# 1high.net
KiCad netlist of a schematic drawn in EAGLE
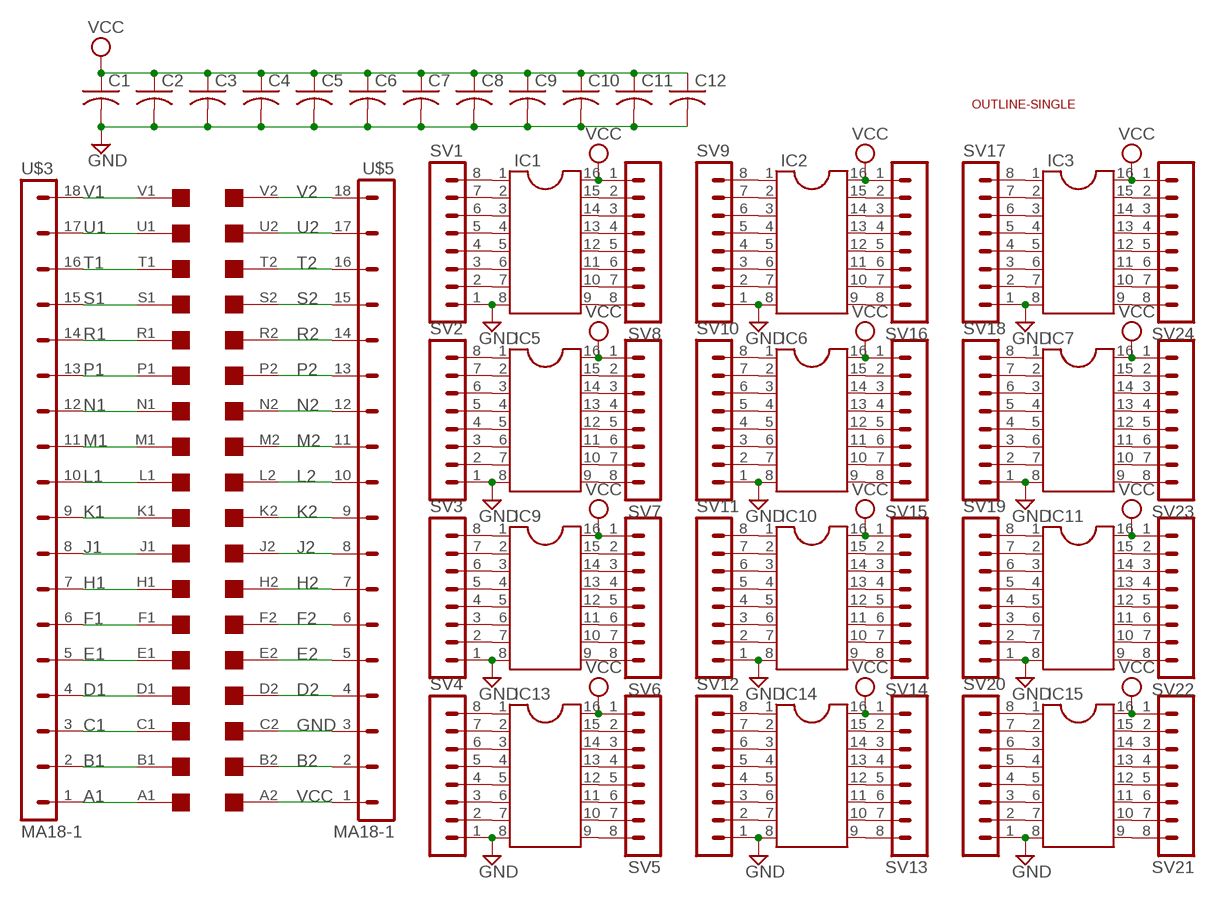
[diagram p0: schematic, sheet 1]

(export (version "E")
  (design (tool "Eeschema 10.0.6"))
  (components
    (comp (ref "C1")
      (value "C-US050-025X075")
      (footprint "eagle-import:C050-025X075")
      (libsource (lib "eagle-import") (part "C-US050-025X075"))
    )
    (comp (ref "C2")
      (value "C-US050-025X075")
      (footprint "eagle-import:C050-025X075")
      (libsource (lib "eagle-import") (part "C-US050-025X075"))
    )
    (comp (ref "C3")
      (value "C-US050-025X075")
      (footprint "eagle-import:C050-025X075")
      (libsource (lib "eagle-import") (part "C-US050-025X075"))
    )
    (comp (ref "C4")
      (value "C-US050-025X075")
      (footprint "eagle-import:C050-025X075")
      (libsource (lib "eagle-import") (part "C-US050-025X075"))
    )
    (comp (ref "C5")
      (value "C-US050-025X075")
      (footprint "eagle-import:C050-025X075")
      (libsource (lib "eagle-import") (part "C-US050-025X075"))
    )
    (comp (ref "C6")
      (value "C-US050-025X075")
      (footprint "eagle-import:C050-025X075")
      (libsource (lib "eagle-import") (part "C-US050-025X075"))
    )
    (comp (ref "C7")
      (value "C-US050-025X075")
      (footprint "eagle-import:C050-025X075")
      (libsource (lib "eagle-import") (part "C-US050-025X075"))
    )
    (comp (ref "C8")
      (value "C-US050-025X075")
      (footprint "eagle-import:C050-025X075")
      (libsource (lib "eagle-import") (part "C-US050-025X075"))
    )
    (comp (ref "C9")
      (value "C-US050-025X075")
      (footprint "eagle-import:C050-025X075")
      (libsource (lib "eagle-import") (part "C-US050-025X075"))
    )
    (comp (ref "C10")
      (value "C-US050-025X075")
      (footprint "eagle-import:C050-025X075")
      (libsource (lib "eagle-import") (part "C-US050-025X075"))
    )
    (comp (ref "C11")
      (value "C-US050-025X075")
      (footprint "eagle-import:C050-025X075")
      (libsource (lib "eagle-import") (part "C-US050-025X075"))
    )
    (comp (ref "C12")
      (value "C-US050-025X075")
      (footprint "eagle-import:C050-025X075")
      (libsource (lib "eagle-import") (part "C-US050-025X075"))
    )
    (comp (ref "IC1")
      (value "DIL16")
      (footprint "eagle-import:DIL16")
      (libsource (lib "eagle-import") (part "DIL16"))
    )
    (comp (ref "IC2")
      (value "DIL16")
      (footprint "eagle-import:DIL16")
      (libsource (lib "eagle-import") (part "DIL16"))
    )
    (comp (ref "IC3")
      (value "DIL16")
      (footprint "eagle-import:DIL16")
      (libsource (lib "eagle-import") (part "DIL16"))
    )
    (comp (ref "IC5")
      (value "DIL16")
      (footprint "eagle-import:DIL16")
      (libsource (lib "eagle-import") (part "DIL16"))
    )
    (comp (ref "IC6")
      (value "DIL16")
      (footprint "eagle-import:DIL16")
      (libsource (lib "eagle-import") (part "DIL16"))
    )
    (comp (ref "IC7")
      (value "DIL16")
      (footprint "eagle-import:DIL16")
      (libsource (lib "eagle-import") (part "DIL16"))
    )
    (comp (ref "IC9")
      (value "DIL16")
      (footprint "eagle-import:DIL16")
      (libsource (lib "eagle-import") (part "DIL16"))
    )
    (comp (ref "IC10")
      (value "DIL16")
      (footprint "eagle-import:DIL16")
      (libsource (lib "eagle-import") (part "DIL16"))
    )
    (comp (ref "IC11")
      (value "DIL16")
      (footprint "eagle-import:DIL16")
      (libsource (lib "eagle-import") (part "DIL16"))
    )
    (comp (ref "IC13")
      (value "DIL16")
      (footprint "eagle-import:DIL16")
      (libsource (lib "eagle-import") (part "DIL16"))
    )
    (comp (ref "IC14")
      (value "DIL16")
      (footprint "eagle-import:DIL16")
      (libsource (lib "eagle-import") (part "DIL16"))
    )
    (comp (ref "IC15")
      (value "DIL16")
      (footprint "eagle-import:DIL16")
      (libsource (lib "eagle-import") (part "DIL16"))
    )
    (comp (ref "SV1")
      (value "MA08-1")
      (footprint "eagle-import:MA08-1")
      (libsource (lib "eagle-import") (part "MA08-1"))
    )
    (comp (ref "SV2")
      (value "MA08-1")
      (footprint "eagle-import:MA08-1")
      (libsource (lib "eagle-import") (part "MA08-1"))
    )
    (comp (ref "SV3")
      (value "MA08-1")
      (footprint "eagle-import:MA08-1")
      (libsource (lib "eagle-import") (part "MA08-1"))
    )
    (comp (ref "SV4")
      (value "MA08-1")
      (footprint "eagle-import:MA08-1")
      (libsource (lib "eagle-import") (part "MA08-1"))
    )
    (comp (ref "SV5")
      (value "MA08-1")
      (footprint "eagle-import:MA08-1")
      (libsource (lib "eagle-import") (part "MA08-1"))
    )
    (comp (ref "SV6")
      (value "MA08-1")
      (footprint "eagle-import:MA08-1")
      (libsource (lib "eagle-import") (part "MA08-1"))
    )
    (comp (ref "SV7")
      (value "MA08-1")
      (footprint "eagle-import:MA08-1")
      (libsource (lib "eagle-import") (part "MA08-1"))
    )
    (comp (ref "SV8")
      (value "MA08-1")
      (footprint "eagle-import:MA08-1")
      (libsource (lib "eagle-import") (part "MA08-1"))
    )
    (comp (ref "SV9")
      (value "MA08-1")
      (footprint "eagle-import:MA08-1")
      (libsource (lib "eagle-import") (part "MA08-1"))
    )
    (comp (ref "SV10")
      (value "MA08-1")
      (footprint "eagle-import:MA08-1")
      (libsource (lib "eagle-import") (part "MA08-1"))
    )
    (comp (ref "SV11")
      (value "MA08-1")
      (footprint "eagle-import:MA08-1")
      (libsource (lib "eagle-import") (part "MA08-1"))
    )
    (comp (ref "SV12")
      (value "MA08-1")
      (footprint "eagle-import:MA08-1")
      (libsource (lib "eagle-import") (part "MA08-1"))
    )
    (comp (ref "SV13")
      (value "MA08-1")
      (footprint "eagle-import:MA08-1")
      (libsource (lib "eagle-import") (part "MA08-1"))
    )
    (comp (ref "SV14")
      (value "MA08-1")
      (footprint "eagle-import:MA08-1")
      (libsource (lib "eagle-import") (part "MA08-1"))
    )
    (comp (ref "SV15")
      (value "MA08-1")
      (footprint "eagle-import:MA08-1")
      (libsource (lib "eagle-import") (part "MA08-1"))
    )
    (comp (ref "SV16")
      (value "MA08-1")
      (footprint "eagle-import:MA08-1")
      (libsource (lib "eagle-import") (part "MA08-1"))
    )
    (comp (ref "SV17")
      (value "MA08-1")
      (footprint "eagle-import:MA08-1")
      (libsource (lib "eagle-import") (part "MA08-1"))
    )
    (comp (ref "SV18")
      (value "MA08-1")
      (footprint "eagle-import:MA08-1")
      (libsource (lib "eagle-import") (part "MA08-1"))
    )
    (comp (ref "SV19")
      (value "MA08-1")
      (footprint "eagle-import:MA08-1")
      (libsource (lib "eagle-import") (part "MA08-1"))
    )
    (comp (ref "SV20")
      (value "MA08-1")
      (footprint "eagle-import:MA08-1")
      (libsource (lib "eagle-import") (part "MA08-1"))
    )
    (comp (ref "SV21")
      (value "MA08-1")
      (footprint "eagle-import:MA08-1")
      (libsource (lib "eagle-import") (part "MA08-1"))
    )
    (comp (ref "SV22")
      (value "MA08-1")
      (footprint "eagle-import:MA08-1")
      (libsource (lib "eagle-import") (part "MA08-1"))
    )
    (comp (ref "SV23")
      (value "MA08-1")
      (footprint "eagle-import:MA08-1")
      (libsource (lib "eagle-import") (part "MA08-1"))
    )
    (comp (ref "SV24")
      (value "MA08-1")
      (footprint "eagle-import:MA08-1")
      (libsource (lib "eagle-import") (part "MA08-1"))
    )
    (comp (ref "U$2")
      (value "OUTLINE-SINGLE")
      (footprint "eagle-import:SINGLE")
      (libsource (lib "eagle-import") (part "OUTLINE-SINGLE"))
    )
    (comp (ref "U$3")
      (value "MA18-1")
      (footprint "eagle-import:MA18-1")
      (libsource (lib "eagle-import") (part "MA18-1"))
    )
    (comp (ref "U$4")
      (value "EDGE-2CONNECTOR")
      (footprint "eagle-import:EDGE-CON2")
      (libsource (lib "eagle-import") (part "EDGE-2CONNECTOR"))
    )
    (comp (ref "U$5")
      (value "MA18-1")
      (footprint "eagle-import:MA18-1")
      (libsource (lib "eagle-import") (part "MA18-1"))
    )
  )
  (nets
    (net (code "1") (name "/A1") (class "Default")
      (node (ref "U$3") (pin "1") (pinfunction "1_1") (pintype "passive"))
      (node (ref "U$4") (pin "A1") (pinfunction "1_A1") (pintype "bidirectional"))
    )
    (net (code "2") (name "/B1") (class "Default")
      (node (ref "U$3") (pin "2") (pinfunction "2_2") (pintype "passive"))
      (node (ref "U$4") (pin "B1") (pinfunction "1_B1") (pintype "bidirectional"))
    )
    (net (code "3") (name "/B2") (class "Default")
      (node (ref "U$4") (pin "B2") (pinfunction "1_B2") (pintype "bidirectional"))
      (node (ref "U$5") (pin "2") (pinfunction "2_2") (pintype "passive"))
    )
    (net (code "4") (name "/C1") (class "Default")
      (node (ref "U$3") (pin "3") (pinfunction "3_3") (pintype "passive"))
      (node (ref "U$4") (pin "C1") (pinfunction "1_C1") (pintype "bidirectional"))
    )
    (net (code "5") (name "/D1") (class "Default")
      (node (ref "U$3") (pin "4") (pinfunction "4_4") (pintype "passive"))
      (node (ref "U$4") (pin "D1") (pinfunction "1_D1") (pintype "bidirectional"))
    )
    (net (code "6") (name "/D2") (class "Default")
      (node (ref "U$4") (pin "D2") (pinfunction "1_D2") (pintype "bidirectional"))
      (node (ref "U$5") (pin "4") (pinfunction "4_4") (pintype "passive"))
    )
    (net (code "7") (name "/E1") (class "Default")
      (node (ref "U$3") (pin "5") (pinfunction "5_5") (pintype "passive"))
      (node (ref "U$4") (pin "E1") (pinfunction "1_E1") (pintype "bidirectional"))
    )
    (net (code "8") (name "/E2") (class "Default")
      (node (ref "U$4") (pin "E2") (pinfunction "1_E2") (pintype "bidirectional"))
      (node (ref "U$5") (pin "5") (pinfunction "5_5") (pintype "passive"))
    )
    (net (code "9") (name "/F1") (class "Default")
      (node (ref "U$3") (pin "6") (pinfunction "6_6") (pintype "passive"))
      (node (ref "U$4") (pin "F1") (pinfunction "1_F1") (pintype "bidirectional"))
    )
    (net (code "10") (name "/F2") (class "Default")
      (node (ref "U$4") (pin "F2") (pinfunction "1_F2") (pintype "bidirectional"))
      (node (ref "U$5") (pin "6") (pinfunction "6_6") (pintype "passive"))
    )
    (net (code "11") (name "/H1") (class "Default")
      (node (ref "U$3") (pin "7") (pinfunction "7_7") (pintype "passive"))
      (node (ref "U$4") (pin "H1") (pinfunction "1_H1") (pintype "bidirectional"))
    )
    (net (code "12") (name "/H2") (class "Default")
      (node (ref "U$4") (pin "H2") (pinfunction "1_H2") (pintype "bidirectional"))
      (node (ref "U$5") (pin "7") (pinfunction "7_7") (pintype "passive"))
    )
    (net (code "13") (name "/J1") (class "Default")
      (node (ref "U$3") (pin "8") (pinfunction "8_8") (pintype "passive"))
      (node (ref "U$4") (pin "J1") (pinfunction "1_J1") (pintype "bidirectional"))
    )
    (net (code "14") (name "/J2") (class "Default")
      (node (ref "U$4") (pin "J2") (pinfunction "1_J2") (pintype "bidirectional"))
      (node (ref "U$5") (pin "8") (pinfunction "8_8") (pintype "passive"))
    )
    (net (code "15") (name "/K1") (class "Default")
      (node (ref "U$3") (pin "9") (pinfunction "9_9") (pintype "passive"))
      (node (ref "U$4") (pin "K1") (pinfunction "1_K1") (pintype "bidirectional"))
    )
    (net (code "16") (name "/K2") (class "Default")
      (node (ref "U$4") (pin "K2") (pinfunction "1_K2") (pintype "bidirectional"))
      (node (ref "U$5") (pin "9") (pinfunction "9_9") (pintype "passive"))
    )
    (net (code "17") (name "/L1") (class "Default")
      (node (ref "U$3") (pin "10") (pinfunction "10_10") (pintype "passive"))
      (node (ref "U$4") (pin "L1") (pinfunction "1_L1") (pintype "bidirectional"))
    )
    (net (code "18") (name "/L2") (class "Default")
      (node (ref "U$4") (pin "L2") (pinfunction "1_L2") (pintype "bidirectional"))
      (node (ref "U$5") (pin "10") (pinfunction "10_10") (pintype "passive"))
    )
    (net (code "19") (name "/M1") (class "Default")
      (node (ref "U$3") (pin "11") (pinfunction "11_11") (pintype "passive"))
      (node (ref "U$4") (pin "M1") (pinfunction "1_M1") (pintype "bidirectional"))
    )
    (net (code "20") (name "/M2") (class "Default")
      (node (ref "U$4") (pin "M2") (pinfunction "1_M2") (pintype "bidirectional"))
      (node (ref "U$5") (pin "11") (pinfunction "11_11") (pintype "passive"))
    )
    (net (code "21") (name "/N1") (class "Default")
      (node (ref "U$3") (pin "12") (pinfunction "12_12") (pintype "passive"))
      (node (ref "U$4") (pin "N1") (pinfunction "1_N1") (pintype "bidirectional"))
    )
    (net (code "22") (name "/N2") (class "Default")
      (node (ref "U$4") (pin "N2") (pinfunction "1_N2") (pintype "bidirectional"))
      (node (ref "U$5") (pin "12") (pinfunction "12_12") (pintype "passive"))
    )
    (net (code "23") (name "/P1") (class "Default")
      (node (ref "U$3") (pin "13") (pinfunction "13_13") (pintype "passive"))
      (node (ref "U$4") (pin "P1") (pinfunction "1_P1") (pintype "bidirectional"))
    )
    (net (code "24") (name "/P2") (class "Default")
      (node (ref "U$4") (pin "P2") (pinfunction "1_P2") (pintype "bidirectional"))
      (node (ref "U$5") (pin "13") (pinfunction "13_13") (pintype "passive"))
    )
    (net (code "25") (name "/R1") (class "Default")
      (node (ref "U$3") (pin "14") (pinfunction "14_14") (pintype "passive"))
      (node (ref "U$4") (pin "R1") (pinfunction "1_R1") (pintype "bidirectional"))
    )
    (net (code "26") (name "/R2") (class "Default")
      (node (ref "U$4") (pin "R2") (pinfunction "1_R2") (pintype "bidirectional"))
      (node (ref "U$5") (pin "14") (pinfunction "14_14") (pintype "passive"))
    )
    (net (code "27") (name "/S1") (class "Default")
      (node (ref "U$3") (pin "15") (pinfunction "15_15") (pintype "passive"))
      (node (ref "U$4") (pin "S1") (pinfunction "1_S1") (pintype "bidirectional"))
    )
    (net (code "28") (name "/S2") (class "Default")
      (node (ref "U$4") (pin "S2") (pinfunction "1_S2") (pintype "bidirectional"))
      (node (ref "U$5") (pin "15") (pinfunction "15_15") (pintype "passive"))
    )
    (net (code "29") (name "/T1") (class "Default")
      (node (ref "U$3") (pin "16") (pinfunction "16_16") (pintype "passive"))
      (node (ref "U$4") (pin "T1") (pinfunction "1_T1") (pintype "bidirectional"))
    )
    (net (code "30") (name "/T2") (class "Default")
      (node (ref "U$4") (pin "T2") (pinfunction "1_T2") (pintype "bidirectional"))
      (node (ref "U$5") (pin "16") (pinfunction "16_16") (pintype "passive"))
    )
    (net (code "31") (name "/U1") (class "Default")
      (node (ref "U$3") (pin "17") (pinfunction "17_17") (pintype "passive"))
      (node (ref "U$4") (pin "U1") (pinfunction "1_U1") (pintype "bidirectional"))
    )
    (net (code "32") (name "/U2") (class "Default")
      (node (ref "U$4") (pin "U2") (pinfunction "1_U2") (pintype "bidirectional"))
      (node (ref "U$5") (pin "17") (pinfunction "17_17") (pintype "passive"))
    )
    (net (code "33") (name "/V1") (class "Default")
      (node (ref "U$3") (pin "18") (pinfunction "18_18") (pintype "passive"))
      (node (ref "U$4") (pin "V1") (pinfunction "1_V1") (pintype "bidirectional"))
    )
    (net (code "34") (name "/V2") (class "Default")
      (node (ref "U$4") (pin "V2") (pinfunction "1_V2") (pintype "bidirectional"))
      (node (ref "U$5") (pin "18") (pinfunction "18_18") (pintype "passive"))
    )
    (net (code "35") (name "GND") (class "Default")
      (node (ref "C1") (pin "2") (pinfunction "2_2") (pintype "passive"))
      (node (ref "C10") (pin "2") (pinfunction "2_2") (pintype "passive"))
      (node (ref "C11") (pin "2") (pinfunction "2_2") (pintype "passive"))
      (node (ref "C12") (pin "2") (pinfunction "2_2") (pintype "passive"))
      (node (ref "C2") (pin "2") (pinfunction "2_2") (pintype "passive"))
      (node (ref "C3") (pin "2") (pinfunction "2_2") (pintype "passive"))
      (node (ref "C4") (pin "2") (pinfunction "2_2") (pintype "passive"))
      (node (ref "C5") (pin "2") (pinfunction "2_2") (pintype "passive"))
      (node (ref "C6") (pin "2") (pinfunction "2_2") (pintype "passive"))
      (node (ref "C7") (pin "2") (pinfunction "2_2") (pintype "passive"))
      (node (ref "C8") (pin "2") (pinfunction "2_2") (pintype "passive"))
      (node (ref "C9") (pin "2") (pinfunction "2_2") (pintype "passive"))
      (node (ref "IC1") (pin "8") (pinfunction "8_8") (pintype "passive"))
      (node (ref "IC10") (pin "8") (pinfunction "8_8") (pintype "passive"))
      (node (ref "IC11") (pin "8") (pinfunction "8_8") (pintype "passive"))
      (node (ref "IC13") (pin "8") (pinfunction "8_8") (pintype "passive"))
      (node (ref "IC14") (pin "8") (pinfunction "8_8") (pintype "passive"))
      (node (ref "IC15") (pin "8") (pinfunction "8_8") (pintype "passive"))
      (node (ref "IC2") (pin "8") (pinfunction "8_8") (pintype "passive"))
      (node (ref "IC3") (pin "8") (pinfunction "8_8") (pintype "passive"))
      (node (ref "IC5") (pin "8") (pinfunction "8_8") (pintype "passive"))
      (node (ref "IC6") (pin "8") (pinfunction "8_8") (pintype "passive"))
      (node (ref "IC7") (pin "8") (pinfunction "8_8") (pintype "passive"))
      (node (ref "IC9") (pin "8") (pinfunction "8_8") (pintype "passive"))
      (node (ref "SV1") (pin "1") (pinfunction "1_1") (pintype "passive"))
      (node (ref "SV10") (pin "1") (pinfunction "1_1") (pintype "passive"))
      (node (ref "SV11") (pin "1") (pinfunction "1_1") (pintype "passive"))
      (node (ref "SV12") (pin "1") (pinfunction "1_1") (pintype "passive"))
      (node (ref "SV17") (pin "1") (pinfunction "1_1") (pintype "passive"))
      (node (ref "SV18") (pin "1") (pinfunction "1_1") (pintype "passive"))
      (node (ref "SV19") (pin "1") (pinfunction "1_1") (pintype "passive"))
      (node (ref "SV2") (pin "1") (pinfunction "1_1") (pintype "passive"))
      (node (ref "SV20") (pin "1") (pinfunction "1_1") (pintype "passive"))
      (node (ref "SV3") (pin "1") (pinfunction "1_1") (pintype "passive"))
      (node (ref "SV4") (pin "1") (pinfunction "1_1") (pintype "passive"))
      (node (ref "SV9") (pin "1") (pinfunction "1_1") (pintype "passive"))
      (node (ref "U$4") (pin "C2") (pinfunction "1_C2") (pintype "bidirectional"))
      (node (ref "U$5") (pin "3") (pinfunction "3_3") (pintype "passive"))
    )
    (net (code "36") (name "Net-(IC1-Pad1)") (class "Default")
      (node (ref "IC1") (pin "1") (pinfunction "1_1") (pintype "passive"))
      (node (ref "SV1") (pin "8") (pinfunction "8_8") (pintype "passive"))
    )
    (net (code "37") (name "Net-(IC1-Pad2)") (class "Default")
      (node (ref "IC1") (pin "2") (pinfunction "2_2") (pintype "passive"))
      (node (ref "SV1") (pin "7") (pinfunction "7_7") (pintype "passive"))
    )
    (net (code "38") (name "Net-(IC1-Pad3)") (class "Default")
      (node (ref "IC1") (pin "3") (pinfunction "3_3") (pintype "passive"))
      (node (ref "SV1") (pin "6") (pinfunction "6_6") (pintype "passive"))
    )
    (net (code "39") (name "Net-(IC1-Pad4)") (class "Default")
      (node (ref "IC1") (pin "4") (pinfunction "4_4") (pintype "passive"))
      (node (ref "SV1") (pin "5") (pinfunction "5_5") (pintype "passive"))
    )
    (net (code "40") (name "Net-(IC1-Pad5)") (class "Default")
      (node (ref "IC1") (pin "5") (pinfunction "5_5") (pintype "passive"))
      (node (ref "SV1") (pin "4") (pinfunction "4_4") (pintype "passive"))
    )
    (net (code "41") (name "Net-(IC1-Pad6)") (class "Default")
      (node (ref "IC1") (pin "6") (pinfunction "6_6") (pintype "passive"))
      (node (ref "SV1") (pin "3") (pinfunction "3_3") (pintype "passive"))
    )
    (net (code "42") (name "Net-(IC1-Pad7)") (class "Default")
      (node (ref "IC1") (pin "7") (pinfunction "7_7") (pintype "passive"))
      (node (ref "SV1") (pin "2") (pinfunction "2_2") (pintype "passive"))
    )
    (net (code "43") (name "Net-(IC1-Pad9)") (class "Default")
      (node (ref "IC1") (pin "9") (pinfunction "9_9") (pintype "passive"))
      (node (ref "SV8") (pin "8") (pinfunction "8_8") (pintype "passive"))
    )
    (net (code "44") (name "Net-(IC1-Pad10)") (class "Default")
      (node (ref "IC1") (pin "10") (pinfunction "10_10") (pintype "passive"))
      (node (ref "SV8") (pin "7") (pinfunction "7_7") (pintype "passive"))
    )
    (net (code "45") (name "Net-(IC1-Pad11)") (class "Default")
      (node (ref "IC1") (pin "11") (pinfunction "11_11") (pintype "passive"))
      (node (ref "SV8") (pin "6") (pinfunction "6_6") (pintype "passive"))
    )
    (net (code "46") (name "Net-(IC1-Pad12)") (class "Default")
      (node (ref "IC1") (pin "12") (pinfunction "12_12") (pintype "passive"))
      (node (ref "SV8") (pin "5") (pinfunction "5_5") (pintype "passive"))
    )
    (net (code "47") (name "Net-(IC1-Pad13)") (class "Default")
      (node (ref "IC1") (pin "13") (pinfunction "13_13") (pintype "passive"))
      (node (ref "SV8") (pin "4") (pinfunction "4_4") (pintype "passive"))
    )
    (net (code "48") (name "Net-(IC1-Pad14)") (class "Default")
      (node (ref "IC1") (pin "14") (pinfunction "14_14") (pintype "passive"))
      (node (ref "SV8") (pin "3") (pinfunction "3_3") (pintype "passive"))
    )
    (net (code "49") (name "Net-(IC1-Pad15)") (class "Default")
      (node (ref "IC1") (pin "15") (pinfunction "15_15") (pintype "passive"))
      (node (ref "SV8") (pin "2") (pinfunction "2_2") (pintype "passive"))
    )
    (net (code "50") (name "Net-(IC2-Pad1)") (class "Default")
      (node (ref "IC2") (pin "1") (pinfunction "1_1") (pintype "passive"))
      (node (ref "SV9") (pin "8") (pinfunction "8_8") (pintype "passive"))
    )
    (net (code "51") (name "Net-(IC2-Pad2)") (class "Default")
      (node (ref "IC2") (pin "2") (pinfunction "2_2") (pintype "passive"))
      (node (ref "SV9") (pin "7") (pinfunction "7_7") (pintype "passive"))
    )
    (net (code "52") (name "Net-(IC2-Pad3)") (class "Default")
      (node (ref "IC2") (pin "3") (pinfunction "3_3") (pintype "passive"))
      (node (ref "SV9") (pin "6") (pinfunction "6_6") (pintype "passive"))
    )
    (net (code "53") (name "Net-(IC2-Pad4)") (class "Default")
      (node (ref "IC2") (pin "4") (pinfunction "4_4") (pintype "passive"))
      (node (ref "SV9") (pin "5") (pinfunction "5_5") (pintype "passive"))
    )
    (net (code "54") (name "Net-(IC2-Pad5)") (class "Default")
      (node (ref "IC2") (pin "5") (pinfunction "5_5") (pintype "passive"))
      (node (ref "SV9") (pin "4") (pinfunction "4_4") (pintype "passive"))
    )
    (net (code "55") (name "Net-(IC2-Pad6)") (class "Default")
      (node (ref "IC2") (pin "6") (pinfunction "6_6") (pintype "passive"))
      (node (ref "SV9") (pin "3") (pinfunction "3_3") (pintype "passive"))
    )
    (net (code "56") (name "Net-(IC2-Pad7)") (class "Default")
      (node (ref "IC2") (pin "7") (pinfunction "7_7") (pintype "passive"))
      (node (ref "SV9") (pin "2") (pinfunction "2_2") (pintype "passive"))
    )
    (net (code "57") (name "Net-(IC2-Pad9)") (class "Default")
      (node (ref "IC2") (pin "9") (pinfunction "9_9") (pintype "passive"))
      (node (ref "SV16") (pin "8") (pinfunction "8_8") (pintype "passive"))
    )
    (net (code "58") (name "Net-(IC2-Pad10)") (class "Default")
      (node (ref "IC2") (pin "10") (pinfunction "10_10") (pintype "passive"))
      (node (ref "SV16") (pin "7") (pinfunction "7_7") (pintype "passive"))
    )
    (net (code "59") (name "Net-(IC2-Pad11)") (class "Default")
      (node (ref "IC2") (pin "11") (pinfunction "11_11") (pintype "passive"))
      (node (ref "SV16") (pin "6") (pinfunction "6_6") (pintype "passive"))
    )
    (net (code "60") (name "Net-(IC2-Pad12)") (class "Default")
      (node (ref "IC2") (pin "12") (pinfunction "12_12") (pintype "passive"))
      (node (ref "SV16") (pin "5") (pinfunction "5_5") (pintype "passive"))
    )
    (net (code "61") (name "Net-(IC2-Pad13)") (class "Default")
      (node (ref "IC2") (pin "13") (pinfunction "13_13") (pintype "passive"))
      (node (ref "SV16") (pin "4") (pinfunction "4_4") (pintype "passive"))
    )
    (net (code "62") (name "Net-(IC2-Pad14)") (class "Default")
      (node (ref "IC2") (pin "14") (pinfunction "14_14") (pintype "passive"))
      (node (ref "SV16") (pin "3") (pinfunction "3_3") (pintype "passive"))
    )
    (net (code "63") (name "Net-(IC2-Pad15)") (class "Default")
      (node (ref "IC2") (pin "15") (pinfunction "15_15") (pintype "passive"))
      (node (ref "SV16") (pin "2") (pinfunction "2_2") (pintype "passive"))
    )
    (net (code "64") (name "Net-(IC3-Pad1)") (class "Default")
      (node (ref "IC3") (pin "1") (pinfunction "1_1") (pintype "passive"))
      (node (ref "SV17") (pin "8") (pinfunction "8_8") (pintype "passive"))
    )
    (net (code "65") (name "Net-(IC3-Pad2)") (class "Default")
      (node (ref "IC3") (pin "2") (pinfunction "2_2") (pintype "passive"))
      (node (ref "SV17") (pin "7") (pinfunction "7_7") (pintype "passive"))
    )
    (net (code "66") (name "Net-(IC3-Pad3)") (class "Default")
      (node (ref "IC3") (pin "3") (pinfunction "3_3") (pintype "passive"))
      (node (ref "SV17") (pin "6") (pinfunction "6_6") (pintype "passive"))
    )
    (net (code "67") (name "Net-(IC3-Pad4)") (class "Default")
      (node (ref "IC3") (pin "4") (pinfunction "4_4") (pintype "passive"))
      (node (ref "SV17") (pin "5") (pinfunction "5_5") (pintype "passive"))
    )
    (net (code "68") (name "Net-(IC3-Pad5)") (class "Default")
      (node (ref "IC3") (pin "5") (pinfunction "5_5") (pintype "passive"))
      (node (ref "SV17") (pin "4") (pinfunction "4_4") (pintype "passive"))
    )
    (net (code "69") (name "Net-(IC3-Pad6)") (class "Default")
      (node (ref "IC3") (pin "6") (pinfunction "6_6") (pintype "passive"))
      (node (ref "SV17") (pin "3") (pinfunction "3_3") (pintype "passive"))
    )
    (net (code "70") (name "Net-(IC3-Pad7)") (class "Default")
      (node (ref "IC3") (pin "7") (pinfunction "7_7") (pintype "passive"))
      (node (ref "SV17") (pin "2") (pinfunction "2_2") (pintype "passive"))
    )
    (net (code "71") (name "Net-(IC3-Pad9)") (class "Default")
      (node (ref "IC3") (pin "9") (pinfunction "9_9") (pintype "passive"))
      (node (ref "SV24") (pin "8") (pinfunction "8_8") (pintype "passive"))
    )
    (net (code "72") (name "Net-(IC3-Pad10)") (class "Default")
      (node (ref "IC3") (pin "10") (pinfunction "10_10") (pintype "passive"))
      (node (ref "SV24") (pin "7") (pinfunction "7_7") (pintype "passive"))
    )
    (net (code "73") (name "Net-(IC3-Pad11)") (class "Default")
      (node (ref "IC3") (pin "11") (pinfunction "11_11") (pintype "passive"))
      (node (ref "SV24") (pin "6") (pinfunction "6_6") (pintype "passive"))
    )
    (net (code "74") (name "Net-(IC3-Pad12)") (class "Default")
      (node (ref "IC3") (pin "12") (pinfunction "12_12") (pintype "passive"))
      (node (ref "SV24") (pin "5") (pinfunction "5_5") (pintype "passive"))
    )
    (net (code "75") (name "Net-(IC3-Pad13)") (class "Default")
      (node (ref "IC3") (pin "13") (pinfunction "13_13") (pintype "passive"))
      (node (ref "SV24") (pin "4") (pinfunction "4_4") (pintype "passive"))
    )
    (net (code "76") (name "Net-(IC3-Pad14)") (class "Default")
      (node (ref "IC3") (pin "14") (pinfunction "14_14") (pintype "passive"))
      (node (ref "SV24") (pin "3") (pinfunction "3_3") (pintype "passive"))
    )
    (net (code "77") (name "Net-(IC3-Pad15)") (class "Default")
      (node (ref "IC3") (pin "15") (pinfunction "15_15") (pintype "passive"))
      (node (ref "SV24") (pin "2") (pinfunction "2_2") (pintype "passive"))
    )
    (net (code "78") (name "Net-(IC5-Pad1)") (class "Default")
      (node (ref "IC5") (pin "1") (pinfunction "1_1") (pintype "passive"))
      (node (ref "SV2") (pin "8") (pinfunction "8_8") (pintype "passive"))
    )
    (net (code "79") (name "Net-(IC5-Pad2)") (class "Default")
      (node (ref "IC5") (pin "2") (pinfunction "2_2") (pintype "passive"))
      (node (ref "SV2") (pin "7") (pinfunction "7_7") (pintype "passive"))
    )
    (net (code "80") (name "Net-(IC5-Pad3)") (class "Default")
      (node (ref "IC5") (pin "3") (pinfunction "3_3") (pintype "passive"))
      (node (ref "SV2") (pin "6") (pinfunction "6_6") (pintype "passive"))
    )
    (net (code "81") (name "Net-(IC5-Pad4)") (class "Default")
      (node (ref "IC5") (pin "4") (pinfunction "4_4") (pintype "passive"))
      (node (ref "SV2") (pin "5") (pinfunction "5_5") (pintype "passive"))
    )
    (net (code "82") (name "Net-(IC5-Pad5)") (class "Default")
      (node (ref "IC5") (pin "5") (pinfunction "5_5") (pintype "passive"))
      (node (ref "SV2") (pin "4") (pinfunction "4_4") (pintype "passive"))
    )
    (net (code "83") (name "Net-(IC5-Pad6)") (class "Default")
      (node (ref "IC5") (pin "6") (pinfunction "6_6") (pintype "passive"))
      (node (ref "SV2") (pin "3") (pinfunction "3_3") (pintype "passive"))
    )
    (net (code "84") (name "Net-(IC5-Pad7)") (class "Default")
      (node (ref "IC5") (pin "7") (pinfunction "7_7") (pintype "passive"))
      (node (ref "SV2") (pin "2") (pinfunction "2_2") (pintype "passive"))
    )
    (net (code "85") (name "Net-(IC5-Pad9)") (class "Default")
      (node (ref "IC5") (pin "9") (pinfunction "9_9") (pintype "passive"))
      (node (ref "SV7") (pin "8") (pinfunction "8_8") (pintype "passive"))
    )
    (net (code "86") (name "Net-(IC5-Pad10)") (class "Default")
      (node (ref "IC5") (pin "10") (pinfunction "10_10") (pintype "passive"))
      (node (ref "SV7") (pin "7") (pinfunction "7_7") (pintype "passive"))
    )
    (net (code "87") (name "Net-(IC5-Pad11)") (class "Default")
      (node (ref "IC5") (pin "11") (pinfunction "11_11") (pintype "passive"))
      (node (ref "SV7") (pin "6") (pinfunction "6_6") (pintype "passive"))
    )
    (net (code "88") (name "Net-(IC5-Pad12)") (class "Default")
      (node (ref "IC5") (pin "12") (pinfunction "12_12") (pintype "passive"))
      (node (ref "SV7") (pin "5") (pinfunction "5_5") (pintype "passive"))
    )
    (net (code "89") (name "Net-(IC5-Pad13)") (class "Default")
      (node (ref "IC5") (pin "13") (pinfunction "13_13") (pintype "passive"))
      (node (ref "SV7") (pin "4") (pinfunction "4_4") (pintype "passive"))
    )
    (net (code "90") (name "Net-(IC5-Pad14)") (class "Default")
      (node (ref "IC5") (pin "14") (pinfunction "14_14") (pintype "passive"))
      (node (ref "SV7") (pin "3") (pinfunction "3_3") (pintype "passive"))
    )
    (net (code "91") (name "Net-(IC5-Pad15)") (class "Default")
      (node (ref "IC5") (pin "15") (pinfunction "15_15") (pintype "passive"))
      (node (ref "SV7") (pin "2") (pinfunction "2_2") (pintype "passive"))
    )
    (net (code "92") (name "Net-(IC6-Pad1)") (class "Default")
      (node (ref "IC6") (pin "1") (pinfunction "1_1") (pintype "passive"))
      (node (ref "SV10") (pin "8") (pinfunction "8_8") (pintype "passive"))
    )
    (net (code "93") (name "Net-(IC6-Pad2)") (class "Default")
      (node (ref "IC6") (pin "2") (pinfunction "2_2") (pintype "passive"))
      (node (ref "SV10") (pin "7") (pinfunction "7_7") (pintype "passive"))
    )
    (net (code "94") (name "Net-(IC6-Pad3)") (class "Default")
      (node (ref "IC6") (pin "3") (pinfunction "3_3") (pintype "passive"))
      (node (ref "SV10") (pin "6") (pinfunction "6_6") (pintype "passive"))
    )
    (net (code "95") (name "Net-(IC6-Pad4)") (class "Default")
      (node (ref "IC6") (pin "4") (pinfunction "4_4") (pintype "passive"))
      (node (ref "SV10") (pin "5") (pinfunction "5_5") (pintype "passive"))
    )
    (net (code "96") (name "Net-(IC6-Pad5)") (class "Default")
      (node (ref "IC6") (pin "5") (pinfunction "5_5") (pintype "passive"))
      (node (ref "SV10") (pin "4") (pinfunction "4_4") (pintype "passive"))
    )
    (net (code "97") (name "Net-(IC6-Pad6)") (class "Default")
      (node (ref "IC6") (pin "6") (pinfunction "6_6") (pintype "passive"))
      (node (ref "SV10") (pin "3") (pinfunction "3_3") (pintype "passive"))
    )
    (net (code "98") (name "Net-(IC6-Pad7)") (class "Default")
      (node (ref "IC6") (pin "7") (pinfunction "7_7") (pintype "passive"))
      (node (ref "SV10") (pin "2") (pinfunction "2_2") (pintype "passive"))
    )
    (net (code "99") (name "Net-(IC6-Pad9)") (class "Default")
      (node (ref "IC6") (pin "9") (pinfunction "9_9") (pintype "passive"))
      (node (ref "SV15") (pin "8") (pinfunction "8_8") (pintype "passive"))
    )
    (net (code "100") (name "Net-(IC6-Pad10)") (class "Default")
      (node (ref "IC6") (pin "10") (pinfunction "10_10") (pintype "passive"))
      (node (ref "SV15") (pin "7") (pinfunction "7_7") (pintype "passive"))
    )
    (net (code "101") (name "Net-(IC6-Pad11)") (class "Default")
      (node (ref "IC6") (pin "11") (pinfunction "11_11") (pintype "passive"))
      (node (ref "SV15") (pin "6") (pinfunction "6_6") (pintype "passive"))
    )
    (net (code "102") (name "Net-(IC6-Pad12)") (class "Default")
      (node (ref "IC6") (pin "12") (pinfunction "12_12") (pintype "passive"))
      (node (ref "SV15") (pin "5") (pinfunction "5_5") (pintype "passive"))
    )
    (net (code "103") (name "Net-(IC6-Pad13)") (class "Default")
      (node (ref "IC6") (pin "13") (pinfunction "13_13") (pintype "passive"))
      (node (ref "SV15") (pin "4") (pinfunction "4_4") (pintype "passive"))
    )
    (net (code "104") (name "Net-(IC6-Pad14)") (class "Default")
      (node (ref "IC6") (pin "14") (pinfunction "14_14") (pintype "passive"))
      (node (ref "SV15") (pin "3") (pinfunction "3_3") (pintype "passive"))
    )
    (net (code "105") (name "Net-(IC6-Pad15)") (class "Default")
      (node (ref "IC6") (pin "15") (pinfunction "15_15") (pintype "passive"))
      (node (ref "SV15") (pin "2") (pinfunction "2_2") (pintype "passive"))
    )
    (net (code "106") (name "Net-(IC7-Pad1)") (class "Default")
      (node (ref "IC7") (pin "1") (pinfunction "1_1") (pintype "passive"))
      (node (ref "SV18") (pin "8") (pinfunction "8_8") (pintype "passive"))
    )
    (net (code "107") (name "Net-(IC7-Pad2)") (class "Default")
      (node (ref "IC7") (pin "2") (pinfunction "2_2") (pintype "passive"))
      (node (ref "SV18") (pin "7") (pinfunction "7_7") (pintype "passive"))
    )
    (net (code "108") (name "Net-(IC7-Pad3)") (class "Default")
      (node (ref "IC7") (pin "3") (pinfunction "3_3") (pintype "passive"))
      (node (ref "SV18") (pin "6") (pinfunction "6_6") (pintype "passive"))
    )
    (net (code "109") (name "Net-(IC7-Pad4)") (class "Default")
      (node (ref "IC7") (pin "4") (pinfunction "4_4") (pintype "passive"))
      (node (ref "SV18") (pin "5") (pinfunction "5_5") (pintype "passive"))
    )
    (net (code "110") (name "Net-(IC7-Pad5)") (class "Default")
      (node (ref "IC7") (pin "5") (pinfunction "5_5") (pintype "passive"))
      (node (ref "SV18") (pin "4") (pinfunction "4_4") (pintype "passive"))
    )
    (net (code "111") (name "Net-(IC7-Pad6)") (class "Default")
      (node (ref "IC7") (pin "6") (pinfunction "6_6") (pintype "passive"))
      (node (ref "SV18") (pin "3") (pinfunction "3_3") (pintype "passive"))
    )
    (net (code "112") (name "Net-(IC7-Pad7)") (class "Default")
      (node (ref "IC7") (pin "7") (pinfunction "7_7") (pintype "passive"))
      (node (ref "SV18") (pin "2") (pinfunction "2_2") (pintype "passive"))
    )
    (net (code "113") (name "Net-(IC7-Pad9)") (class "Default")
      (node (ref "IC7") (pin "9") (pinfunction "9_9") (pintype "passive"))
      (node (ref "SV23") (pin "8") (pinfunction "8_8") (pintype "passive"))
    )
    (net (code "114") (name "Net-(IC7-Pad10)") (class "Default")
      (node (ref "IC7") (pin "10") (pinfunction "10_10") (pintype "passive"))
      (node (ref "SV23") (pin "7") (pinfunction "7_7") (pintype "passive"))
    )
    (net (code "115") (name "Net-(IC7-Pad11)") (class "Default")
      (node (ref "IC7") (pin "11") (pinfunction "11_11") (pintype "passive"))
      (node (ref "SV23") (pin "6") (pinfunction "6_6") (pintype "passive"))
    )
    (net (code "116") (name "Net-(IC7-Pad12)") (class "Default")
      (node (ref "IC7") (pin "12") (pinfunction "12_12") (pintype "passive"))
      (node (ref "SV23") (pin "5") (pinfunction "5_5") (pintype "passive"))
    )
    (net (code "117") (name "Net-(IC7-Pad13)") (class "Default")
      (node (ref "IC7") (pin "13") (pinfunction "13_13") (pintype "passive"))
      (node (ref "SV23") (pin "4") (pinfunction "4_4") (pintype "passive"))
    )
    (net (code "118") (name "Net-(IC7-Pad14)") (class "Default")
      (node (ref "IC7") (pin "14") (pinfunction "14_14") (pintype "passive"))
      (node (ref "SV23") (pin "3") (pinfunction "3_3") (pintype "passive"))
    )
    (net (code "119") (name "Net-(IC7-Pad15)") (class "Default")
      (node (ref "IC7") (pin "15") (pinfunction "15_15") (pintype "passive"))
      (node (ref "SV23") (pin "2") (pinfunction "2_2") (pintype "passive"))
    )
    (net (code "120") (name "Net-(IC9-Pad1)") (class "Default")
      (node (ref "IC9") (pin "1") (pinfunction "1_1") (pintype "passive"))
      (node (ref "SV3") (pin "8") (pinfunction "8_8") (pintype "passive"))
    )
    (net (code "121") (name "Net-(IC9-Pad2)") (class "Default")
      (node (ref "IC9") (pin "2") (pinfunction "2_2") (pintype "passive"))
      (node (ref "SV3") (pin "7") (pinfunction "7_7") (pintype "passive"))
    )
    (net (code "122") (name "Net-(IC9-Pad3)") (class "Default")
      (node (ref "IC9") (pin "3") (pinfunction "3_3") (pintype "passive"))
      (node (ref "SV3") (pin "6") (pinfunction "6_6") (pintype "passive"))
    )
    (net (code "123") (name "Net-(IC9-Pad4)") (class "Default")
      (node (ref "IC9") (pin "4") (pinfunction "4_4") (pintype "passive"))
      (node (ref "SV3") (pin "5") (pinfunction "5_5") (pintype "passive"))
    )
    (net (code "124") (name "Net-(IC9-Pad5)") (class "Default")
      (node (ref "IC9") (pin "5") (pinfunction "5_5") (pintype "passive"))
      (node (ref "SV3") (pin "4") (pinfunction "4_4") (pintype "passive"))
    )
    (net (code "125") (name "Net-(IC9-Pad6)") (class "Default")
      (node (ref "IC9") (pin "6") (pinfunction "6_6") (pintype "passive"))
      (node (ref "SV3") (pin "3") (pinfunction "3_3") (pintype "passive"))
    )
    (net (code "126") (name "Net-(IC9-Pad7)") (class "Default")
      (node (ref "IC9") (pin "7") (pinfunction "7_7") (pintype "passive"))
      (node (ref "SV3") (pin "2") (pinfunction "2_2") (pintype "passive"))
    )
    (net (code "127") (name "Net-(IC9-Pad9)") (class "Default")
      (node (ref "IC9") (pin "9") (pinfunction "9_9") (pintype "passive"))
      (node (ref "SV6") (pin "8") (pinfunction "8_8") (pintype "passive"))
    )
    (net (code "128") (name "Net-(IC9-Pad10)") (class "Default")
      (node (ref "IC9") (pin "10") (pinfunction "10_10") (pintype "passive"))
      (node (ref "SV6") (pin "7") (pinfunction "7_7") (pintype "passive"))
    )
    (net (code "129") (name "Net-(IC9-Pad11)") (class "Default")
      (node (ref "IC9") (pin "11") (pinfunction "11_11") (pintype "passive"))
      (node (ref "SV6") (pin "6") (pinfunction "6_6") (pintype "passive"))
    )
    (net (code "130") (name "Net-(IC9-Pad12)") (class "Default")
      (node (ref "IC9") (pin "12") (pinfunction "12_12") (pintype "passive"))
      (node (ref "SV6") (pin "5") (pinfunction "5_5") (pintype "passive"))
    )
    (net (code "131") (name "Net-(IC9-Pad13)") (class "Default")
      (node (ref "IC9") (pin "13") (pinfunction "13_13") (pintype "passive"))
      (node (ref "SV6") (pin "4") (pinfunction "4_4") (pintype "passive"))
    )
    (net (code "132") (name "Net-(IC9-Pad14)") (class "Default")
      (node (ref "IC9") (pin "14") (pinfunction "14_14") (pintype "passive"))
      (node (ref "SV6") (pin "3") (pinfunction "3_3") (pintype "passive"))
    )
    (net (code "133") (name "Net-(IC9-Pad15)") (class "Default")
      (node (ref "IC9") (pin "15") (pinfunction "15_15") (pintype "passive"))
      (node (ref "SV6") (pin "2") (pinfunction "2_2") (pintype "passive"))
    )
    (net (code "134") (name "Net-(IC10-Pad1)") (class "Default")
      (node (ref "IC10") (pin "1") (pinfunction "1_1") (pintype "passive"))
      (node (ref "SV11") (pin "8") (pinfunction "8_8") (pintype "passive"))
    )
    (net (code "135") (name "Net-(IC10-Pad2)") (class "Default")
      (node (ref "IC10") (pin "2") (pinfunction "2_2") (pintype "passive"))
      (node (ref "SV11") (pin "7") (pinfunction "7_7") (pintype "passive"))
    )
    (net (code "136") (name "Net-(IC10-Pad3)") (class "Default")
      (node (ref "IC10") (pin "3") (pinfunction "3_3") (pintype "passive"))
      (node (ref "SV11") (pin "6") (pinfunction "6_6") (pintype "passive"))
    )
    (net (code "137") (name "Net-(IC10-Pad4)") (class "Default")
      (node (ref "IC10") (pin "4") (pinfunction "4_4") (pintype "passive"))
      (node (ref "SV11") (pin "5") (pinfunction "5_5") (pintype "passive"))
    )
    (net (code "138") (name "Net-(IC10-Pad5)") (class "Default")
      (node (ref "IC10") (pin "5") (pinfunction "5_5") (pintype "passive"))
      (node (ref "SV11") (pin "4") (pinfunction "4_4") (pintype "passive"))
    )
    (net (code "139") (name "Net-(IC10-Pad6)") (class "Default")
      (node (ref "IC10") (pin "6") (pinfunction "6_6") (pintype "passive"))
      (node (ref "SV11") (pin "3") (pinfunction "3_3") (pintype "passive"))
    )
    (net (code "140") (name "Net-(IC10-Pad7)") (class "Default")
      (node (ref "IC10") (pin "7") (pinfunction "7_7") (pintype "passive"))
      (node (ref "SV11") (pin "2") (pinfunction "2_2") (pintype "passive"))
    )
    (net (code "141") (name "Net-(IC10-Pad9)") (class "Default")
      (node (ref "IC10") (pin "9") (pinfunction "9_9") (pintype "passive"))
      (node (ref "SV14") (pin "8") (pinfunction "8_8") (pintype "passive"))
    )
    (net (code "142") (name "Net-(IC10-Pad10)") (class "Default")
      (node (ref "IC10") (pin "10") (pinfunction "10_10") (pintype "passive"))
      (node (ref "SV14") (pin "7") (pinfunction "7_7") (pintype "passive"))
    )
    (net (code "143") (name "Net-(IC10-Pad11)") (class "Default")
      (node (ref "IC10") (pin "11") (pinfunction "11_11") (pintype "passive"))
      (node (ref "SV14") (pin "6") (pinfunction "6_6") (pintype "passive"))
    )
    (net (code "144") (name "Net-(IC10-Pad12)") (class "Default")
      (node (ref "IC10") (pin "12") (pinfunction "12_12") (pintype "passive"))
      (node (ref "SV14") (pin "5") (pinfunction "5_5") (pintype "passive"))
    )
    (net (code "145") (name "Net-(IC10-Pad13)") (class "Default")
      (node (ref "IC10") (pin "13") (pinfunction "13_13") (pintype "passive"))
      (node (ref "SV14") (pin "4") (pinfunction "4_4") (pintype "passive"))
    )
    (net (code "146") (name "Net-(IC10-Pad14)") (class "Default")
      (node (ref "IC10") (pin "14") (pinfunction "14_14") (pintype "passive"))
      (node (ref "SV14") (pin "3") (pinfunction "3_3") (pintype "passive"))
    )
    (net (code "147") (name "Net-(IC10-Pad15)") (class "Default")
      (node (ref "IC10") (pin "15") (pinfunction "15_15") (pintype "passive"))
      (node (ref "SV14") (pin "2") (pinfunction "2_2") (pintype "passive"))
    )
    (net (code "148") (name "Net-(IC11-Pad1)") (class "Default")
      (node (ref "IC11") (pin "1") (pinfunction "1_1") (pintype "passive"))
      (node (ref "SV19") (pin "8") (pinfunction "8_8") (pintype "passive"))
    )
    (net (code "149") (name "Net-(IC11-Pad2)") (class "Default")
      (node (ref "IC11") (pin "2") (pinfunction "2_2") (pintype "passive"))
      (node (ref "SV19") (pin "7") (pinfunction "7_7") (pintype "passive"))
    )
    (net (code "150") (name "Net-(IC11-Pad3)") (class "Default")
      (node (ref "IC11") (pin "3") (pinfunction "3_3") (pintype "passive"))
      (node (ref "SV19") (pin "6") (pinfunction "6_6") (pintype "passive"))
    )
    (net (code "151") (name "Net-(IC11-Pad4)") (class "Default")
      (node (ref "IC11") (pin "4") (pinfunction "4_4") (pintype "passive"))
      (node (ref "SV19") (pin "5") (pinfunction "5_5") (pintype "passive"))
    )
    (net (code "152") (name "Net-(IC11-Pad5)") (class "Default")
      (node (ref "IC11") (pin "5") (pinfunction "5_5") (pintype "passive"))
      (node (ref "SV19") (pin "4") (pinfunction "4_4") (pintype "passive"))
    )
    (net (code "153") (name "Net-(IC11-Pad6)") (class "Default")
      (node (ref "IC11") (pin "6") (pinfunction "6_6") (pintype "passive"))
      (node (ref "SV19") (pin "3") (pinfunction "3_3") (pintype "passive"))
    )
    (net (code "154") (name "Net-(IC11-Pad7)") (class "Default")
      (node (ref "IC11") (pin "7") (pinfunction "7_7") (pintype "passive"))
      (node (ref "SV19") (pin "2") (pinfunction "2_2") (pintype "passive"))
    )
    (net (code "155") (name "Net-(IC11-Pad9)") (class "Default")
      (node (ref "IC11") (pin "9") (pinfunction "9_9") (pintype "passive"))
      (node (ref "SV22") (pin "8") (pinfunction "8_8") (pintype "passive"))
    )
    (net (code "156") (name "Net-(IC11-Pad10)") (class "Default")
      (node (ref "IC11") (pin "10") (pinfunction "10_10") (pintype "passive"))
      (node (ref "SV22") (pin "7") (pinfunction "7_7") (pintype "passive"))
    )
    (net (code "157") (name "Net-(IC11-Pad11)") (class "Default")
      (node (ref "IC11") (pin "11") (pinfunction "11_11") (pintype "passive"))
      (node (ref "SV22") (pin "6") (pinfunction "6_6") (pintype "passive"))
    )
    (net (code "158") (name "Net-(IC11-Pad12)") (class "Default")
      (node (ref "IC11") (pin "12") (pinfunction "12_12") (pintype "passive"))
      (node (ref "SV22") (pin "5") (pinfunction "5_5") (pintype "passive"))
    )
    (net (code "159") (name "Net-(IC11-Pad13)") (class "Default")
      (node (ref "IC11") (pin "13") (pinfunction "13_13") (pintype "passive"))
      (node (ref "SV22") (pin "4") (pinfunction "4_4") (pintype "passive"))
    )
    (net (code "160") (name "Net-(IC11-Pad14)") (class "Default")
      (node (ref "IC11") (pin "14") (pinfunction "14_14") (pintype "passive"))
      (node (ref "SV22") (pin "3") (pinfunction "3_3") (pintype "passive"))
    )
    (net (code "161") (name "Net-(IC11-Pad15)") (class "Default")
      (node (ref "IC11") (pin "15") (pinfunction "15_15") (pintype "passive"))
      (node (ref "SV22") (pin "2") (pinfunction "2_2") (pintype "passive"))
    )
    (net (code "162") (name "Net-(IC13-Pad1)") (class "Default")
      (node (ref "IC13") (pin "1") (pinfunction "1_1") (pintype "passive"))
      (node (ref "SV4") (pin "8") (pinfunction "8_8") (pintype "passive"))
    )
    (net (code "163") (name "Net-(IC13-Pad2)") (class "Default")
      (node (ref "IC13") (pin "2") (pinfunction "2_2") (pintype "passive"))
      (node (ref "SV4") (pin "7") (pinfunction "7_7") (pintype "passive"))
    )
    (net (code "164") (name "Net-(IC13-Pad3)") (class "Default")
      (node (ref "IC13") (pin "3") (pinfunction "3_3") (pintype "passive"))
      (node (ref "SV4") (pin "6") (pinfunction "6_6") (pintype "passive"))
    )
    (net (code "165") (name "Net-(IC13-Pad4)") (class "Default")
      (node (ref "IC13") (pin "4") (pinfunction "4_4") (pintype "passive"))
      (node (ref "SV4") (pin "5") (pinfunction "5_5") (pintype "passive"))
    )
    (net (code "166") (name "Net-(IC13-Pad5)") (class "Default")
      (node (ref "IC13") (pin "5") (pinfunction "5_5") (pintype "passive"))
      (node (ref "SV4") (pin "4") (pinfunction "4_4") (pintype "passive"))
    )
    (net (code "167") (name "Net-(IC13-Pad6)") (class "Default")
      (node (ref "IC13") (pin "6") (pinfunction "6_6") (pintype "passive"))
      (node (ref "SV4") (pin "3") (pinfunction "3_3") (pintype "passive"))
    )
    (net (code "168") (name "Net-(IC13-Pad7)") (class "Default")
      (node (ref "IC13") (pin "7") (pinfunction "7_7") (pintype "passive"))
      (node (ref "SV4") (pin "2") (pinfunction "2_2") (pintype "passive"))
    )
    (net (code "169") (name "Net-(IC13-Pad9)") (class "Default")
      (node (ref "IC13") (pin "9") (pinfunction "9_9") (pintype "passive"))
      (node (ref "SV5") (pin "8") (pinfunction "8_8") (pintype "passive"))
    )
    (net (code "170") (name "Net-(IC13-Pad10)") (class "Default")
      (node (ref "IC13") (pin "10") (pinfunction "10_10") (pintype "passive"))
      (node (ref "SV5") (pin "7") (pinfunction "7_7") (pintype "passive"))
    )
    (net (code "171") (name "Net-(IC13-Pad11)") (class "Default")
      (node (ref "IC13") (pin "11") (pinfunction "11_11") (pintype "passive"))
      (node (ref "SV5") (pin "6") (pinfunction "6_6") (pintype "passive"))
    )
    (net (code "172") (name "Net-(IC13-Pad12)") (class "Default")
      (node (ref "IC13") (pin "12") (pinfunction "12_12") (pintype "passive"))
      (node (ref "SV5") (pin "5") (pinfunction "5_5") (pintype "passive"))
    )
    (net (code "173") (name "Net-(IC13-Pad13)") (class "Default")
      (node (ref "IC13") (pin "13") (pinfunction "13_13") (pintype "passive"))
      (node (ref "SV5") (pin "4") (pinfunction "4_4") (pintype "passive"))
    )
    (net (code "174") (name "Net-(IC13-Pad14)") (class "Default")
      (node (ref "IC13") (pin "14") (pinfunction "14_14") (pintype "passive"))
      (node (ref "SV5") (pin "3") (pinfunction "3_3") (pintype "passive"))
    )
    (net (code "175") (name "Net-(IC13-Pad15)") (class "Default")
      (node (ref "IC13") (pin "15") (pinfunction "15_15") (pintype "passive"))
      (node (ref "SV5") (pin "2") (pinfunction "2_2") (pintype "passive"))
    )
    (net (code "176") (name "Net-(IC14-Pad1)") (class "Default")
      (node (ref "IC14") (pin "1") (pinfunction "1_1") (pintype "passive"))
      (node (ref "SV12") (pin "8") (pinfunction "8_8") (pintype "passive"))
    )
    (net (code "177") (name "Net-(IC14-Pad2)") (class "Default")
      (node (ref "IC14") (pin "2") (pinfunction "2_2") (pintype "passive"))
      (node (ref "SV12") (pin "7") (pinfunction "7_7") (pintype "passive"))
    )
    (net (code "178") (name "Net-(IC14-Pad3)") (class "Default")
      (node (ref "IC14") (pin "3") (pinfunction "3_3") (pintype "passive"))
      (node (ref "SV12") (pin "6") (pinfunction "6_6") (pintype "passive"))
    )
    (net (code "179") (name "Net-(IC14-Pad4)") (class "Default")
      (node (ref "IC14") (pin "4") (pinfunction "4_4") (pintype "passive"))
      (node (ref "SV12") (pin "5") (pinfunction "5_5") (pintype "passive"))
    )
    (net (code "180") (name "Net-(IC14-Pad5)") (class "Default")
      (node (ref "IC14") (pin "5") (pinfunction "5_5") (pintype "passive"))
      (node (ref "SV12") (pin "4") (pinfunction "4_4") (pintype "passive"))
    )
    (net (code "181") (name "Net-(IC14-Pad6)") (class "Default")
      (node (ref "IC14") (pin "6") (pinfunction "6_6") (pintype "passive"))
      (node (ref "SV12") (pin "3") (pinfunction "3_3") (pintype "passive"))
    )
    (net (code "182") (name "Net-(IC14-Pad7)") (class "Default")
      (node (ref "IC14") (pin "7") (pinfunction "7_7") (pintype "passive"))
      (node (ref "SV12") (pin "2") (pinfunction "2_2") (pintype "passive"))
    )
    (net (code "183") (name "Net-(IC14-Pad9)") (class "Default")
      (node (ref "IC14") (pin "9") (pinfunction "9_9") (pintype "passive"))
      (node (ref "SV13") (pin "8") (pinfunction "8_8") (pintype "passive"))
    )
    (net (code "184") (name "Net-(IC14-Pad10)") (class "Default")
      (node (ref "IC14") (pin "10") (pinfunction "10_10") (pintype "passive"))
      (node (ref "SV13") (pin "7") (pinfunction "7_7") (pintype "passive"))
    )
    (net (code "185") (name "Net-(IC14-Pad11)") (class "Default")
      (node (ref "IC14") (pin "11") (pinfunction "11_11") (pintype "passive"))
      (node (ref "SV13") (pin "6") (pinfunction "6_6") (pintype "passive"))
    )
    (net (code "186") (name "Net-(IC14-Pad12)") (class "Default")
      (node (ref "IC14") (pin "12") (pinfunction "12_12") (pintype "passive"))
      (node (ref "SV13") (pin "5") (pinfunction "5_5") (pintype "passive"))
    )
    (net (code "187") (name "Net-(IC14-Pad13)") (class "Default")
      (node (ref "IC14") (pin "13") (pinfunction "13_13") (pintype "passive"))
      (node (ref "SV13") (pin "4") (pinfunction "4_4") (pintype "passive"))
    )
    (net (code "188") (name "Net-(IC14-Pad14)") (class "Default")
      (node (ref "IC14") (pin "14") (pinfunction "14_14") (pintype "passive"))
      (node (ref "SV13") (pin "3") (pinfunction "3_3") (pintype "passive"))
    )
    (net (code "189") (name "Net-(IC14-Pad15)") (class "Default")
      (node (ref "IC14") (pin "15") (pinfunction "15_15") (pintype "passive"))
      (node (ref "SV13") (pin "2") (pinfunction "2_2") (pintype "passive"))
    )
    (net (code "190") (name "Net-(IC15-Pad1)") (class "Default")
      (node (ref "IC15") (pin "1") (pinfunction "1_1") (pintype "passive"))
      (node (ref "SV20") (pin "8") (pinfunction "8_8") (pintype "passive"))
    )
    (net (code "191") (name "Net-(IC15-Pad2)") (class "Default")
      (node (ref "IC15") (pin "2") (pinfunction "2_2") (pintype "passive"))
      (node (ref "SV20") (pin "7") (pinfunction "7_7") (pintype "passive"))
    )
    (net (code "192") (name "Net-(IC15-Pad3)") (class "Default")
      (node (ref "IC15") (pin "3") (pinfunction "3_3") (pintype "passive"))
      (node (ref "SV20") (pin "6") (pinfunction "6_6") (pintype "passive"))
    )
    (net (code "193") (name "Net-(IC15-Pad4)") (class "Default")
      (node (ref "IC15") (pin "4") (pinfunction "4_4") (pintype "passive"))
      (node (ref "SV20") (pin "5") (pinfunction "5_5") (pintype "passive"))
    )
    (net (code "194") (name "Net-(IC15-Pad5)") (class "Default")
      (node (ref "IC15") (pin "5") (pinfunction "5_5") (pintype "passive"))
      (node (ref "SV20") (pin "4") (pinfunction "4_4") (pintype "passive"))
    )
    (net (code "195") (name "Net-(IC15-Pad6)") (class "Default")
      (node (ref "IC15") (pin "6") (pinfunction "6_6") (pintype "passive"))
      (node (ref "SV20") (pin "3") (pinfunction "3_3") (pintype "passive"))
    )
    (net (code "196") (name "Net-(IC15-Pad7)") (class "Default")
      (node (ref "IC15") (pin "7") (pinfunction "7_7") (pintype "passive"))
      (node (ref "SV20") (pin "2") (pinfunction "2_2") (pintype "passive"))
    )
    (net (code "197") (name "Net-(IC15-Pad9)") (class "Default")
      (node (ref "IC15") (pin "9") (pinfunction "9_9") (pintype "passive"))
      (node (ref "SV21") (pin "8") (pinfunction "8_8") (pintype "passive"))
    )
    (net (code "198") (name "Net-(IC15-Pad10)") (class "Default")
      (node (ref "IC15") (pin "10") (pinfunction "10_10") (pintype "passive"))
      (node (ref "SV21") (pin "7") (pinfunction "7_7") (pintype "passive"))
    )
    (net (code "199") (name "Net-(IC15-Pad11)") (class "Default")
      (node (ref "IC15") (pin "11") (pinfunction "11_11") (pintype "passive"))
      (node (ref "SV21") (pin "6") (pinfunction "6_6") (pintype "passive"))
    )
    (net (code "200") (name "Net-(IC15-Pad12)") (class "Default")
      (node (ref "IC15") (pin "12") (pinfunction "12_12") (pintype "passive"))
      (node (ref "SV21") (pin "5") (pinfunction "5_5") (pintype "passive"))
    )
    (net (code "201") (name "Net-(IC15-Pad13)") (class "Default")
      (node (ref "IC15") (pin "13") (pinfunction "13_13") (pintype "passive"))
      (node (ref "SV21") (pin "4") (pinfunction "4_4") (pintype "passive"))
    )
    (net (code "202") (name "Net-(IC15-Pad14)") (class "Default")
      (node (ref "IC15") (pin "14") (pinfunction "14_14") (pintype "passive"))
      (node (ref "SV21") (pin "3") (pinfunction "3_3") (pintype "passive"))
    )
    (net (code "203") (name "Net-(IC15-Pad15)") (class "Default")
      (node (ref "IC15") (pin "15") (pinfunction "15_15") (pintype "passive"))
      (node (ref "SV21") (pin "2") (pinfunction "2_2") (pintype "passive"))
    )
    (net (code "204") (name "VCC") (class "Default")
      (node (ref "C1") (pin "1") (pinfunction "1_1") (pintype "passive"))
      (node (ref "C10") (pin "1") (pinfunction "1_1") (pintype "passive"))
      (node (ref "C11") (pin "1") (pinfunction "1_1") (pintype "passive"))
      (node (ref "C12") (pin "1") (pinfunction "1_1") (pintype "passive"))
      (node (ref "C2") (pin "1") (pinfunction "1_1") (pintype "passive"))
      (node (ref "C3") (pin "1") (pinfunction "1_1") (pintype "passive"))
      (node (ref "C4") (pin "1") (pinfunction "1_1") (pintype "passive"))
      (node (ref "C5") (pin "1") (pinfunction "1_1") (pintype "passive"))
      (node (ref "C6") (pin "1") (pinfunction "1_1") (pintype "passive"))
      (node (ref "C7") (pin "1") (pinfunction "1_1") (pintype "passive"))
      (node (ref "C8") (pin "1") (pinfunction "1_1") (pintype "passive"))
      (node (ref "C9") (pin "1") (pinfunction "1_1") (pintype "passive"))
      (node (ref "IC1") (pin "16") (pinfunction "16_16") (pintype "passive"))
      (node (ref "IC10") (pin "16") (pinfunction "16_16") (pintype "passive"))
      (node (ref "IC11") (pin "16") (pinfunction "16_16") (pintype "passive"))
      (node (ref "IC13") (pin "16") (pinfunction "16_16") (pintype "passive"))
      (node (ref "IC14") (pin "16") (pinfunction "16_16") (pintype "passive"))
      (node (ref "IC15") (pin "16") (pinfunction "16_16") (pintype "passive"))
      (node (ref "IC2") (pin "16") (pinfunction "16_16") (pintype "passive"))
      (node (ref "IC3") (pin "16") (pinfunction "16_16") (pintype "passive"))
      (node (ref "IC5") (pin "16") (pinfunction "16_16") (pintype "passive"))
      (node (ref "IC6") (pin "16") (pinfunction "16_16") (pintype "passive"))
      (node (ref "IC7") (pin "16") (pinfunction "16_16") (pintype "passive"))
      (node (ref "IC9") (pin "16") (pinfunction "16_16") (pintype "passive"))
      (node (ref "SV13") (pin "1") (pinfunction "1_1") (pintype "passive"))
      (node (ref "SV14") (pin "1") (pinfunction "1_1") (pintype "passive"))
      (node (ref "SV15") (pin "1") (pinfunction "1_1") (pintype "passive"))
      (node (ref "SV16") (pin "1") (pinfunction "1_1") (pintype "passive"))
      (node (ref "SV21") (pin "1") (pinfunction "1_1") (pintype "passive"))
      (node (ref "SV22") (pin "1") (pinfunction "1_1") (pintype "passive"))
      (node (ref "SV23") (pin "1") (pinfunction "1_1") (pintype "passive"))
      (node (ref "SV24") (pin "1") (pinfunction "1_1") (pintype "passive"))
      (node (ref "SV5") (pin "1") (pinfunction "1_1") (pintype "passive"))
      (node (ref "SV6") (pin "1") (pinfunction "1_1") (pintype "passive"))
      (node (ref "SV7") (pin "1") (pinfunction "1_1") (pintype "passive"))
      (node (ref "SV8") (pin "1") (pinfunction "1_1") (pintype "passive"))
      (node (ref "U$4") (pin "A2") (pinfunction "1_A2") (pintype "bidirectional"))
      (node (ref "U$5") (pin "1") (pinfunction "1_1") (pintype "passive"))
    )
  )
)
